# temp_board1_-_itr2_V2.net
KiCad netlist of a schematic drawn in EAGLE
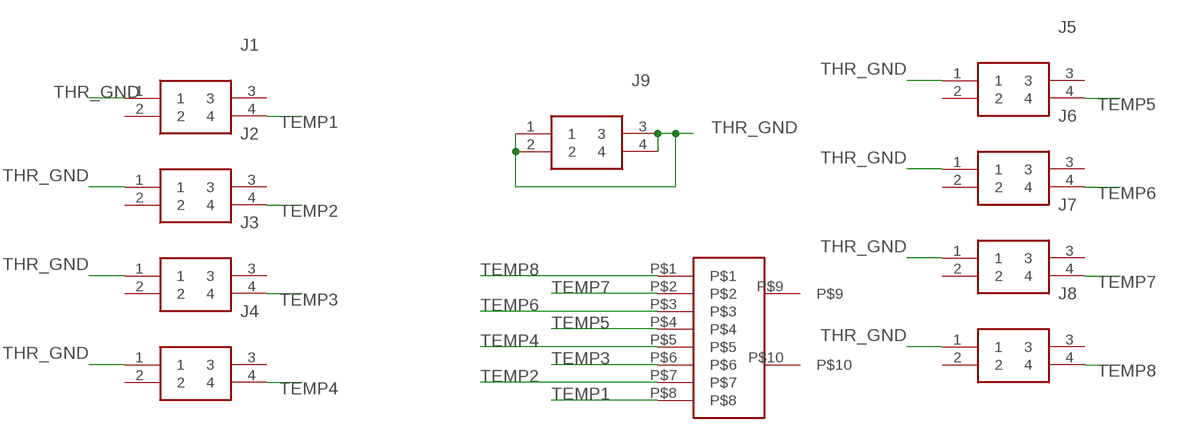
[diagram p0: schematic, sheet 1]

(export (version "E")
  (design (tool "Eeschema 10.0.6"))
  (components
    (comp (ref "J1")
      (value "43045-0415")
      (footprint "eagle-import:43045-04YY_15,16,17")
      (fields (field (name "MOUSER_PART_NUMBER") "538-43045-0415"))
      (libsource (lib "eagle-import") (part "43045-0415"))
    )
    (comp (ref "J2")
      (value "43045-0415")
      (footprint "eagle-import:43045-04YY_15,16,17")
      (fields (field (name "MOUSER_PART_NUMBER") "538-43045-0415"))
      (libsource (lib "eagle-import") (part "43045-0415"))
    )
    (comp (ref "J3")
      (value "43045-0415")
      (footprint "eagle-import:43045-04YY_15,16,17")
      (fields (field (name "MOUSER_PART_NUMBER") "538-43045-0415"))
      (libsource (lib "eagle-import") (part "43045-0415"))
    )
    (comp (ref "J4")
      (value "43045-0415")
      (footprint "eagle-import:43045-04YY_15,16,17")
      (fields (field (name "MOUSER_PART_NUMBER") "538-43045-0415"))
      (libsource (lib "eagle-import") (part "43045-0415"))
    )
    (comp (ref "J5")
      (value "43045-0415")
      (footprint "eagle-import:43045-04YY_15,16,17")
      (fields (field (name "MOUSER_PART_NUMBER") "538-43045-0415"))
      (libsource (lib "eagle-import") (part "43045-0415"))
    )
    (comp (ref "J6")
      (value "43045-0415")
      (footprint "eagle-import:43045-04YY_15,16,17")
      (fields (field (name "MOUSER_PART_NUMBER") "538-43045-0415"))
      (libsource (lib "eagle-import") (part "43045-0415"))
    )
    (comp (ref "J7")
      (value "43045-0415")
      (footprint "eagle-import:43045-04YY_15,16,17")
      (fields (field (name "MOUSER_PART_NUMBER") "538-43045-0415"))
      (libsource (lib "eagle-import") (part "43045-0415"))
    )
    (comp (ref "J8")
      (value "43045-0415")
      (footprint "eagle-import:43045-04YY_15,16,17")
      (fields (field (name "MOUSER_PART_NUMBER") "538-43045-0415"))
      (libsource (lib "eagle-import") (part "43045-0415"))
    )
    (comp (ref "J9")
      (value "43045-0415")
      (footprint "eagle-import:43045-04YY_15,16,17")
      (fields (field (name "MOUSER_PART_NUMBER") "538-43045-0415"))
      (libsource (lib "eagle-import") (part "43045-0415"))
    )
    (comp (ref "U$35")
      (value "VERTICALBMS8")
      (footprint "eagle-import:VERTICALBMS8")
      (libsource (lib "eagle-import") (part "VERTICALBMS8"))
    )
  )
  (nets
    (net (code "1") (name "/TEMP1") (class "Default")
      (node (ref "J1") (pin "4") (pinfunction "4_4") (pintype "bidirectional"))
      (node (ref "U$35") (pin "P$8") (pinfunction "P$8_P$8") (pintype "bidirectional"))
    )
    (net (code "2") (name "/TEMP2") (class "Default")
      (node (ref "J2") (pin "4") (pinfunction "4_4") (pintype "bidirectional"))
      (node (ref "U$35") (pin "P$7") (pinfunction "P$7_P$7") (pintype "bidirectional"))
    )
    (net (code "3") (name "/TEMP3") (class "Default")
      (node (ref "J3") (pin "4") (pinfunction "4_4") (pintype "bidirectional"))
      (node (ref "U$35") (pin "P$6") (pinfunction "P$6_P$6") (pintype "bidirectional"))
    )
    (net (code "4") (name "/TEMP4") (class "Default")
      (node (ref "J4") (pin "4") (pinfunction "4_4") (pintype "bidirectional"))
      (node (ref "U$35") (pin "P$5") (pinfunction "P$5_P$5") (pintype "bidirectional"))
    )
    (net (code "5") (name "/TEMP5") (class "Default")
      (node (ref "J5") (pin "4") (pinfunction "4_4") (pintype "bidirectional"))
      (node (ref "U$35") (pin "P$4") (pinfunction "P$4_P$4") (pintype "bidirectional"))
    )
    (net (code "6") (name "/TEMP6") (class "Default")
      (node (ref "J6") (pin "4") (pinfunction "4_4") (pintype "bidirectional"))
      (node (ref "U$35") (pin "P$3") (pinfunction "P$3_P$3") (pintype "bidirectional"))
    )
    (net (code "7") (name "/TEMP7") (class "Default")
      (node (ref "J7") (pin "4") (pinfunction "4_4") (pintype "bidirectional"))
      (node (ref "U$35") (pin "P$2") (pinfunction "P$2_P$2") (pintype "bidirectional"))
    )
    (net (code "8") (name "/TEMP8") (class "Default")
      (node (ref "J8") (pin "4") (pinfunction "4_4") (pintype "bidirectional"))
      (node (ref "U$35") (pin "P$1") (pinfunction "P$1_P$1") (pintype "bidirectional"))
    )
    (net (code "9") (name "/THR_GND") (class "Default")
      (node (ref "J1") (pin "1") (pinfunction "1_1") (pintype "bidirectional"))
      (node (ref "J2") (pin "1") (pinfunction "1_1") (pintype "bidirectional"))
      (node (ref "J3") (pin "1") (pinfunction "1_1") (pintype "bidirectional"))
      (node (ref "J4") (pin "1") (pinfunction "1_1") (pintype "bidirectional"))
      (node (ref "J5") (pin "1") (pinfunction "1_1") (pintype "bidirectional"))
      (node (ref "J6") (pin "1") (pinfunction "1_1") (pintype "bidirectional"))
      (node (ref "J7") (pin "1") (pinfunction "1_1") (pintype "bidirectional"))
      (node (ref "J8") (pin "1") (pinfunction "1_1") (pintype "bidirectional"))
      (node (ref "J9") (pin "1") (pinfunction "1_1") (pintype "bidirectional"))
      (node (ref "J9") (pin "2") (pinfunction "2_2") (pintype "bidirectional"))
      (node (ref "J9") (pin "3") (pinfunction "3_3") (pintype "bidirectional"))
      (node (ref "J9") (pin "4") (pinfunction "4_4") (pintype "bidirectional"))
    )
    (net (code "10") (name "unconnected-(J1-Pad2)") (class "Default")
      (node (ref "J1") (pin "2") (pinfunction "2_2") (pintype "bidirectional"))
    )
    (net (code "11") (name "unconnected-(J1-Pad3)") (class "Default")
      (node (ref "J1") (pin "3") (pinfunction "3_3") (pintype "bidirectional"))
    )
    (net (code "12") (name "unconnected-(J2-Pad2)") (class "Default")
      (node (ref "J2") (pin "2") (pinfunction "2_2") (pintype "bidirectional"))
    )
    (net (code "13") (name "unconnected-(J2-Pad3)") (class "Default")
      (node (ref "J2") (pin "3") (pinfunction "3_3") (pintype "bidirectional"))
    )
    (net (code "14") (name "unconnected-(J3-Pad2)") (class "Default")
      (node (ref "J3") (pin "2") (pinfunction "2_2") (pintype "bidirectional"))
    )
    (net (code "15") (name "unconnected-(J3-Pad3)") (class "Default")
      (node (ref "J3") (pin "3") (pinfunction "3_3") (pintype "bidirectional"))
    )
    (net (code "16") (name "unconnected-(J4-Pad2)") (class "Default")
      (node (ref "J4") (pin "2") (pinfunction "2_2") (pintype "bidirectional"))
    )
    (net (code "17") (name "unconnected-(J4-Pad3)") (class "Default")
      (node (ref "J4") (pin "3") (pinfunction "3_3") (pintype "bidirectional"))
    )
    (net (code "18") (name "unconnected-(J5-Pad2)") (class "Default")
      (node (ref "J5") (pin "2") (pinfunction "2_2") (pintype "bidirectional"))
    )
    (net (code "19") (name "unconnected-(J5-Pad3)") (class "Default")
      (node (ref "J5") (pin "3") (pinfunction "3_3") (pintype "bidirectional"))
    )
    (net (code "20") (name "unconnected-(J6-Pad2)") (class "Default")
      (node (ref "J6") (pin "2") (pinfunction "2_2") (pintype "bidirectional"))
    )
    (net (code "21") (name "unconnected-(J6-Pad3)") (class "Default")
      (node (ref "J6") (pin "3") (pinfunction "3_3") (pintype "bidirectional"))
    )
    (net (code "22") (name "unconnected-(J7-Pad2)") (class "Default")
      (node (ref "J7") (pin "2") (pinfunction "2_2") (pintype "bidirectional"))
    )
    (net (code "23") (name "unconnected-(J7-Pad3)") (class "Default")
      (node (ref "J7") (pin "3") (pinfunction "3_3") (pintype "bidirectional"))
    )
    (net (code "24") (name "unconnected-(J8-Pad2)") (class "Default")
      (node (ref "J8") (pin "2") (pinfunction "2_2") (pintype "bidirectional"))
    )
    (net (code "25") (name "unconnected-(J8-Pad3)") (class "Default")
      (node (ref "J8") (pin "3") (pinfunction "3_3") (pintype "bidirectional"))
    )
    (net (code "26") (name "unconnected-(U$35-PadP$9)") (class "Default")
      (node (ref "U$35") (pin "P$9") (pinfunction "P$9_P$9") (pintype "bidirectional"))
    )
    (net (code "27") (name "unconnected-(U$35-PadP$10)") (class "Default")
      (node (ref "U$35") (pin "P$10") (pinfunction "P$10_P$10") (pintype "bidirectional"))
    )
  )
)
